# Processor_Interface.net
KiCad netlist of a schematic drawn in Altium Designer
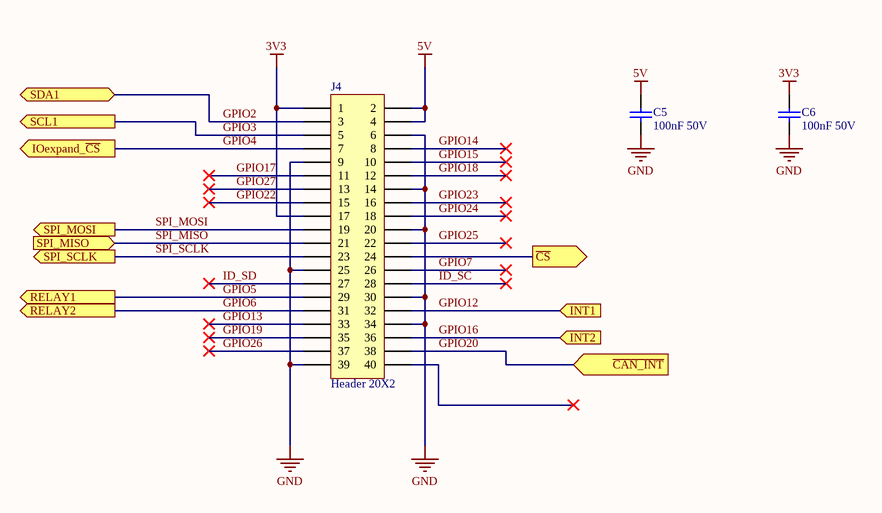
[diagram p0: Processor_Interface.SchDoc]

(export (version "E")
  (design (tool "Eeschema 10.0.6"))
  (components
    (comp (ref "C5")
      (value "100nF 50V")
      (footprint "WCT:0603C_L")
      (fields
        (field (name "MANUFACTURER") "Yageo")
        (field (name "MANUFACTURER PART NUMBER") "CC0603ZRY5V9BB104")
        (field (name "TOLERANCE") "-20%, +80%")
      )
      (libsource (lib "WCT") (part "Cap100nF_50V_0603"))
    )
    (comp (ref "C6")
      (value "100nF 50V")
      (footprint "0603C_L")
      (fields
        (field (name "MANUFACTURER") "Yageo")
        (field (name "MANUFACTURER PART NUMBER") "CC0603ZRY5V9BB104")
        (field (name "TOLERANCE") "-20%, +80%")
      )
      (libsource (lib "WCT") (part "Cap100nF_50V_0603"))
    )
    (comp (ref "J4")
      (value "Header 20X2")
      (footprint "HDR2X20")
      (description "Header, 20-Pin, Dual row")
      (fields (field (name "PUBLISHER") "Altium Limited"))
      (libsource (lib "Miscellaneous Connectors") (part "Header 20X2"))
    )
  )
  (nets
    (net (code "1") (name "/GPIO2") (class "Default")
      (node (ref "J4") (pin "3") (pinfunction "3_3") (pintype "passive"))
    )
    (net (code "2") (name "/GPIO3") (class "Default")
      (node (ref "J4") (pin "5") (pinfunction "5_5") (pintype "passive"))
    )
    (net (code "3") (name "/GPIO4") (class "Default")
      (node (ref "J4") (pin "7") (pinfunction "7_7") (pintype "passive"))
    )
    (net (code "4") (name "/GPIO5") (class "Default")
      (node (ref "J4") (pin "29") (pinfunction "29_29") (pintype "passive"))
    )
    (net (code "5") (name "/GPIO6") (class "Default")
      (node (ref "J4") (pin "31") (pinfunction "31_31") (pintype "passive"))
    )
    (net (code "6") (name "/GPIO7") (class "Default")
      (node (ref "J4") (pin "26") (pinfunction "26_26") (pintype "passive+no_connect"))
    )
    (net (code "7") (name "/GPIO12") (class "Default")
      (node (ref "J4") (pin "32") (pinfunction "32_32") (pintype "passive"))
    )
    (net (code "8") (name "/GPIO13") (class "Default")
      (node (ref "J4") (pin "33") (pinfunction "33_33") (pintype "passive+no_connect"))
    )
    (net (code "9") (name "/GPIO14") (class "Default")
      (node (ref "J4") (pin "8") (pinfunction "8_8") (pintype "passive+no_connect"))
    )
    (net (code "10") (name "/GPIO15") (class "Default")
      (node (ref "J4") (pin "10") (pinfunction "10_10") (pintype "passive+no_connect"))
    )
    (net (code "11") (name "/GPIO16") (class "Default")
      (node (ref "J4") (pin "36") (pinfunction "36_36") (pintype "passive"))
    )
    (net (code "12") (name "/GPIO17") (class "Default")
      (node (ref "J4") (pin "11") (pinfunction "11_11") (pintype "passive+no_connect"))
    )
    (net (code "13") (name "/GPIO18") (class "Default")
      (node (ref "J4") (pin "12") (pinfunction "12_12") (pintype "passive+no_connect"))
    )
    (net (code "14") (name "/GPIO19") (class "Default")
      (node (ref "J4") (pin "35") (pinfunction "35_35") (pintype "passive+no_connect"))
    )
    (net (code "15") (name "/GPIO20") (class "Default")
      (node (ref "J4") (pin "38") (pinfunction "38_38") (pintype "passive"))
    )
    (net (code "16") (name "/GPIO22") (class "Default")
      (node (ref "J4") (pin "15") (pinfunction "15_15") (pintype "passive+no_connect"))
    )
    (net (code "17") (name "/GPIO23") (class "Default")
      (node (ref "J4") (pin "16") (pinfunction "16_16") (pintype "passive+no_connect"))
    )
    (net (code "18") (name "/GPIO24") (class "Default")
      (node (ref "J4") (pin "18") (pinfunction "18_18") (pintype "passive+no_connect"))
    )
    (net (code "19") (name "/GPIO25") (class "Default")
      (node (ref "J4") (pin "22") (pinfunction "22_22") (pintype "passive+no_connect"))
    )
    (net (code "20") (name "/GPIO26") (class "Default")
      (node (ref "J4") (pin "37") (pinfunction "37_37") (pintype "passive+no_connect"))
    )
    (net (code "21") (name "/GPIO27") (class "Default")
      (node (ref "J4") (pin "13") (pinfunction "13_13") (pintype "passive+no_connect"))
    )
    (net (code "22") (name "/ID_SC") (class "Default")
      (node (ref "J4") (pin "28") (pinfunction "28_28") (pintype "passive+no_connect"))
    )
    (net (code "23") (name "/ID_SD") (class "Default")
      (node (ref "J4") (pin "27") (pinfunction "27_27") (pintype "passive+no_connect"))
    )
    (net (code "24") (name "/SPI_MISO") (class "Default")
      (node (ref "J4") (pin "21") (pinfunction "21_21") (pintype "passive"))
    )
    (net (code "25") (name "/SPI_MOSI") (class "Default")
      (node (ref "J4") (pin "19") (pinfunction "19_19") (pintype "passive"))
    )
    (net (code "26") (name "/SPI_SCLK") (class "Default")
      (node (ref "J4") (pin "23") (pinfunction "23_23") (pintype "passive"))
    )
    (net (code "27") (name "/~{CS}") (class "Default")
      (node (ref "J4") (pin "24") (pinfunction "24_24") (pintype "passive"))
    )
    (net (code "28") (name "3V3") (class "Default")
      (node (ref "C6") (pin "2") (pinfunction "2_2") (pintype "passive"))
      (node (ref "J4") (pin "1") (pinfunction "1_1") (pintype "passive"))
      (node (ref "J4") (pin "17") (pinfunction "17_17") (pintype "passive"))
    )
    (net (code "29") (name "5V") (class "Default")
      (node (ref "C5") (pin "2") (pinfunction "2_2") (pintype "passive"))
      (node (ref "J4") (pin "2") (pinfunction "2_2") (pintype "passive"))
      (node (ref "J4") (pin "4") (pinfunction "4_4") (pintype "passive"))
    )
    (net (code "30") (name "GND") (class "Default")
      (node (ref "C5") (pin "1") (pinfunction "1_1") (pintype "passive"))
      (node (ref "C6") (pin "1") (pinfunction "1_1") (pintype "passive"))
      (node (ref "J4") (pin "14") (pinfunction "14_14") (pintype "passive"))
      (node (ref "J4") (pin "20") (pinfunction "20_20") (pintype "passive"))
      (node (ref "J4") (pin "25") (pinfunction "25_25") (pintype "passive"))
      (node (ref "J4") (pin "30") (pinfunction "30_30") (pintype "passive"))
      (node (ref "J4") (pin "34") (pinfunction "34_34") (pintype "passive"))
      (node (ref "J4") (pin "39") (pinfunction "39_39") (pintype "passive"))
      (node (ref "J4") (pin "6") (pinfunction "6_6") (pintype "passive"))
      (node (ref "J4") (pin "9") (pinfunction "9_9") (pintype "passive"))
    )
    (net (code "31") (name "unconnected-(J4-Pad40)") (class "Default")
      (node (ref "J4") (pin "40") (pinfunction "40_40") (pintype "passive+no_connect"))
    )
  )
)
